# LCD.net
KiCad netlist of a schematic drawn in Altium Designer
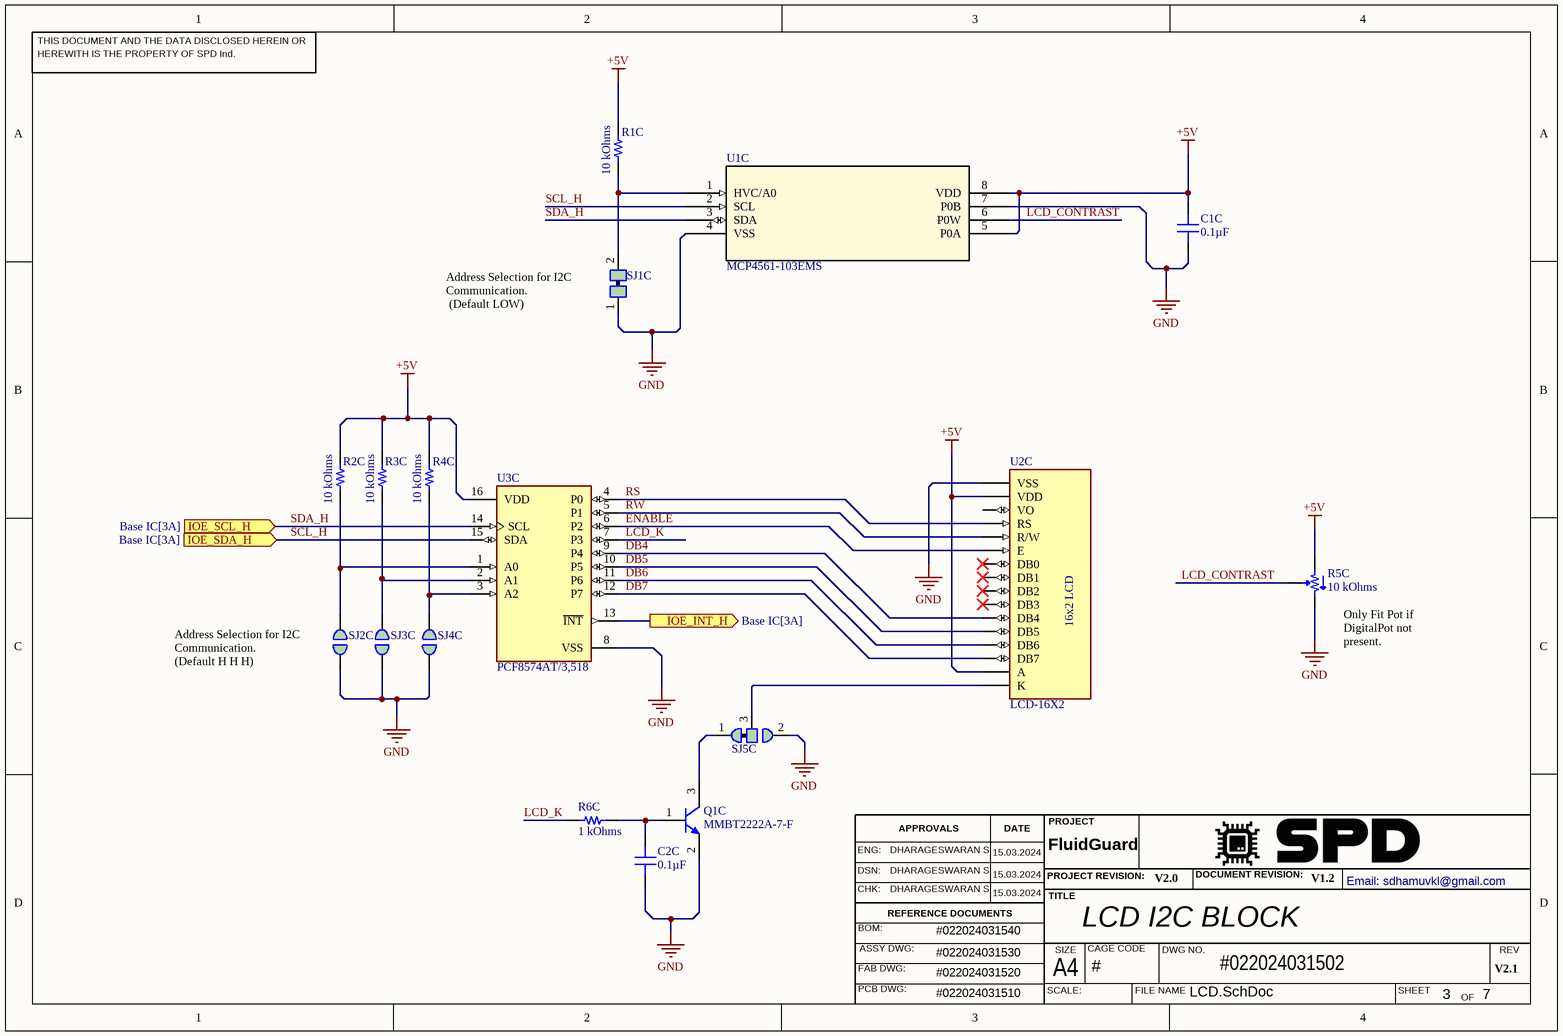
[diagram p0: LCD.SchDoc]

(export (version "E")
  (design (tool "Eeschema 10.0.6"))
  (components
    (comp (ref "C1C")
      (value "0.1µF")
      (footprint "CAP 0402_1005")
      (description "CAP CER 0.1UF 16V X7R 0402")
      (fields (field (name "PART NUMBER") "0402YC104KAT2A") (field (name "MANUFACTURER") "AVX Corporation"))
      (libsource (lib "Postgres Altium Library - altium_library") (part "Capacitor"))
    )
    (comp (ref "C2C")
      (value "0.1µF")
      (footprint "CAP 0402_1005")
      (description "CAP CER 0.1UF 16V X7R 0402")
      (fields (field (name "PART NUMBER") "0402YC104KAT2A") (field (name "MANUFACTURER") "AVX Corporation"))
      (libsource (lib "Postgres Altium Library - altium_library") (part "Capacitor"))
    )
    (comp (ref "Q1C")
      (value "MMBT2222A-7-F")
      (footprint "DIODES SOT-23-3")
      (description "TRANS NPN 40V 0.6A SOT23-3")
      (fields (field (name "MANUFACTURER") "Diodes Incorporated"))
      (libsource (lib "Postgres Altium Library - altium_library") (part "DIODES INC NPN SOT-23-3"))
    )
    (comp (ref "R1C")
      (value "10 kOhms")
      (footprint "RES 0402_1005")
      (description "RES 10K OHM 1% 1/16W 0402")
      (fields (field (name "PART NUMBER") "AC0402FR-1310KL") (field (name "TOLERANCE") "±1%"))
      (libsource (lib "Postgres Altium Library - altium_library") (part "Resistor"))
    )
    (comp (ref "R2C")
      (value "10 kOhms")
      (footprint "RES 0402_1005")
      (description "RES 10K OHM 1% 1/16W 0402")
      (fields (field (name "PART NUMBER") "AC0402FR-1310KL") (field (name "TOLERANCE") "±1%"))
      (libsource (lib "Postgres Altium Library - altium_library") (part "Resistor"))
    )
    (comp (ref "R3C")
      (value "10 kOhms")
      (footprint "RES 0402_1005")
      (description "RES 10K OHM 1% 1/16W 0402")
      (fields (field (name "PART NUMBER") "AC0402FR-1310KL") (field (name "TOLERANCE") "±1%"))
      (libsource (lib "Postgres Altium Library - altium_library") (part "Resistor"))
    )
    (comp (ref "R4C")
      (value "10 kOhms")
      (footprint "RES 0402_1005")
      (description "RES 10K OHM 1% 1/16W 0402")
      (fields (field (name "PART NUMBER") "AC0402FR-1310KL") (field (name "TOLERANCE") "±1%"))
      (libsource (lib "Postgres Altium Library - altium_library") (part "Resistor"))
    )
    (comp (ref "R5C")
      (value "10 kOhms")
      (footprint "BOURNS TRIMPOT 3299P")
      (description "TRIMMER 10K OHM 0.5W PC PIN SIDE")
      (fields (field (name "PART NUMBER") "3299P-1-103LF") (field (name "TOLERANCE") "±10%"))
      (libsource (lib "Postgres Altium Library - altium_library") (part "Potentiometer"))
    )
    (comp (ref "R6C")
      (value "1 kOhms")
      (footprint "RES 0402_1005")
      (description "RES 1K OHM 0.5% 1/16W 0402")
      (fields (field (name "PART NUMBER") "AC0402DR-071KL") (field (name "TOLERANCE") "±0.5%"))
      (libsource (lib "Postgres Altium Library - altium_library") (part "Resistor"))
    )
    (comp (ref "SJ1C")
      (value "2PIN")
      (footprint "Rectangular Jumper Joint")
      (libsource (lib "Jumper-SMD") (part "Regtangular Jumper Joint"))
    )
    (comp (ref "SJ2C")
      (value "2PIN")
      (footprint "Rounded Jumper")
      (libsource (lib "Jumper-SMD") (part "Rounded Jumper"))
    )
    (comp (ref "SJ3C")
      (value "2PIN")
      (footprint "Rounded Jumper")
      (libsource (lib "Jumper-SMD") (part "Rounded Jumper"))
    )
    (comp (ref "SJ4C")
      (value "2PIN")
      (footprint "Rounded Jumper")
      (libsource (lib "Jumper-SMD") (part "Rounded Jumper"))
    )
    (comp (ref "SJ5C")
      (value "3PIN")
      (footprint "Rounded Jumper Joint 3-pin")
      (libsource (lib "Jumper-SMD") (part "Rounded Jumper Joint 3-pin"))
    )
    (comp (ref "U1C")
      (value "MCP4561-103EMS")
      (footprint "MSOP8_MC_MCH")
      (description "No Description Available")
      (libsource (lib "MCP4561-103EMS") (part "MCP4561-103EMS"))
    )
    (comp (ref "U2C")
      (value "LCD-16X2")
      (footprint "LCD-16X2 Pin")
      (description "Display Development Tools 16x2 Black on Green Char LCD w Backlight")
      (fields (field (name "MF") "Gravitech"))
      (libsource (lib "LCD16X2_PIN") (part "LCD-16X2"))
    )
    (comp (ref "U3C")
      (value "PCF8574AT/3,518")
      (footprint "FP-SOT162-1-MFG")
      (description "IC I/O EXPANDER I2C 8B 16SOIC")
      (fields
        (field (name "MANUFACTURER") "NXP Semiconductors")
        (field (name "OCTOPART") "https://octopart.com/pcf8574at%2F3%2C518-nxp+semiconductors-11541925")
      )
      (libsource (lib "Altium Content Vault") (part "f7fde53ce59de981fb0b266a4e103eb"))
    )
  )
  (nets
    (net (code "1") (name "+5V") (class "Default")
      (node (ref "C1C") (pin "2") (pinfunction "2_2") (pintype "passive"))
      (node (ref "R1C") (pin "2") (pinfunction "2_2") (pintype "passive"))
      (node (ref "R2C") (pin "2") (pinfunction "2_2") (pintype "passive"))
      (node (ref "R3C") (pin "2") (pinfunction "2_2") (pintype "passive"))
      (node (ref "R4C") (pin "2") (pinfunction "2_2") (pintype "passive"))
      (node (ref "R5C") (pin "1") (pinfunction "1_1") (pintype "passive"))
      (node (ref "U1C") (pin "5") (pinfunction "P0A_5") (pintype "passive"))
      (node (ref "U1C") (pin "8") (pinfunction "VDD_8") (pintype "power_in"))
      (node (ref "U2C") (pin "15") (pinfunction "A_15") (pintype "power_in"))
      (node (ref "U2C") (pin "2") (pinfunction "VDD_2") (pintype "power_in"))
      (node (ref "U3C") (pin "16") (pinfunction "VDD_16") (pintype "power_in"))
    )
    (net (code "2") (name "/DB4") (class "Default")
      (node (ref "U2C") (pin "11") (pinfunction "DB4_11") (pintype "bidirectional"))
      (node (ref "U3C") (pin "9") (pinfunction "P4_9") (pintype "bidirectional"))
    )
    (net (code "3") (name "/DB5") (class "Default")
      (node (ref "U2C") (pin "12") (pinfunction "DB5_12") (pintype "bidirectional"))
      (node (ref "U3C") (pin "10") (pinfunction "P5_10") (pintype "bidirectional"))
    )
    (net (code "4") (name "/DB6") (class "Default")
      (node (ref "U2C") (pin "13") (pinfunction "DB6_13") (pintype "bidirectional"))
      (node (ref "U3C") (pin "11") (pinfunction "P6_11") (pintype "bidirectional"))
    )
    (net (code "5") (name "/DB7") (class "Default")
      (node (ref "U2C") (pin "14") (pinfunction "DB7_14") (pintype "bidirectional"))
      (node (ref "U3C") (pin "12") (pinfunction "P7_12") (pintype "bidirectional"))
    )
    (net (code "6") (name "/ENABLE") (class "Default")
      (node (ref "U2C") (pin "6") (pinfunction "E_6") (pintype "input"))
      (node (ref "U3C") (pin "6") (pinfunction "P2_6") (pintype "bidirectional"))
    )
    (net (code "7") (name "/IOE_INT_H") (class "Default")
      (node (ref "U3C") (pin "13") (pinfunction "~{INT}_13") (pintype "output"))
    )
    (net (code "8") (name "/LCD_CONTRAST") (class "Default")
      (node (ref "R5C") (pin "2") (pinfunction "2_2") (pintype "passive"))
      (node (ref "U1C") (pin "6") (pinfunction "P0W_6") (pintype "passive"))
    )
    (net (code "9") (name "/LCD_K") (class "Default")
      (node (ref "R6C") (pin "1") (pinfunction "1_1") (pintype "passive"))
      (node (ref "U3C") (pin "7") (pinfunction "P3_7") (pintype "bidirectional"))
    )
    (net (code "10") (name "/RS") (class "Default")
      (node (ref "U2C") (pin "4") (pinfunction "RS_4") (pintype "input"))
      (node (ref "U3C") (pin "4") (pinfunction "P0_4") (pintype "bidirectional"))
    )
    (net (code "11") (name "/RW") (class "Default")
      (node (ref "U2C") (pin "5") (pinfunction "R/W_5") (pintype "input"))
      (node (ref "U3C") (pin "5") (pinfunction "P1_5") (pintype "bidirectional"))
    )
    (net (code "12") (name "/SCL_H") (class "Default")
      (node (ref "U1C") (pin "2") (pinfunction "SCL_2") (pintype "input"))
      (node (ref "U3C") (pin "15") (pinfunction "SDA_15") (pintype "bidirectional"))
    )
    (net (code "13") (name "/SDA_H") (class "Default")
      (node (ref "U1C") (pin "3") (pinfunction "SDA_3") (pintype "bidirectional"))
      (node (ref "U3C") (pin "14") (pinfunction "SCL_14") (pintype "input"))
    )
    (net (code "14") (name "GND") (class "Default")
      (node (ref "C1C") (pin "1") (pinfunction "1_1") (pintype "passive"))
      (node (ref "C2C") (pin "1") (pinfunction "1_1") (pintype "passive"))
      (node (ref "Q1C") (pin "2") (pinfunction "E_2") (pintype "passive"))
      (node (ref "R5C") (pin "3") (pinfunction "3_3") (pintype "passive"))
      (node (ref "SJ1C") (pin "1") (pinfunction "1_1") (pintype "passive"))
      (node (ref "SJ2C") (pin "1") (pinfunction "1_1") (pintype "passive"))
      (node (ref "SJ3C") (pin "1") (pinfunction "1_1") (pintype "passive"))
      (node (ref "SJ4C") (pin "1") (pinfunction "1_1") (pintype "passive"))
      (node (ref "SJ5C") (pin "2") (pinfunction "2_2") (pintype "passive"))
      (node (ref "U1C") (pin "4") (pinfunction "VSS_4") (pintype "power_in"))
      (node (ref "U1C") (pin "7") (pinfunction "P0B_7") (pintype "passive"))
      (node (ref "U2C") (pin "1") (pinfunction "VSS_1") (pintype "power_in"))
      (node (ref "U3C") (pin "8") (pinfunction "VSS_8") (pintype "power_in"))
    )
    (net (code "15") (name "Net-(Q1C-B)") (class "Default")
      (node (ref "C2C") (pin "2") (pinfunction "2_2") (pintype "passive"))
      (node (ref "Q1C") (pin "1") (pinfunction "B_1") (pintype "passive"))
      (node (ref "R6C") (pin "2") (pinfunction "2_2") (pintype "passive"))
    )
    (net (code "16") (name "Net-(Q1C-C)") (class "Default")
      (node (ref "Q1C") (pin "3") (pinfunction "C_3") (pintype "passive"))
      (node (ref "SJ5C") (pin "1") (pinfunction "1_1") (pintype "passive"))
    )
    (net (code "17") (name "Net-(U1C-HVC{slash}A0)") (class "Default")
      (node (ref "R1C") (pin "1") (pinfunction "1_1") (pintype "passive"))
      (node (ref "SJ1C") (pin "2") (pinfunction "2_2") (pintype "passive"))
      (node (ref "U1C") (pin "1") (pinfunction "HVC/A0_1") (pintype "input"))
    )
    (net (code "18") (name "Net-(U2C-K)") (class "Default")
      (node (ref "SJ5C") (pin "3") (pinfunction "3_3") (pintype "passive"))
      (node (ref "U2C") (pin "16") (pinfunction "K_16") (pintype "power_in"))
    )
    (net (code "19") (name "Net-(U3C-A0)") (class "Default")
      (node (ref "R2C") (pin "1") (pinfunction "1_1") (pintype "passive"))
      (node (ref "SJ2C") (pin "2") (pinfunction "2_2") (pintype "passive"))
      (node (ref "U3C") (pin "1") (pinfunction "A0_1") (pintype "input"))
    )
    (net (code "20") (name "Net-(U3C-A1)") (class "Default")
      (node (ref "R3C") (pin "1") (pinfunction "1_1") (pintype "passive"))
      (node (ref "SJ3C") (pin "2") (pinfunction "2_2") (pintype "passive"))
      (node (ref "U3C") (pin "2") (pinfunction "A1_2") (pintype "input"))
    )
    (net (code "21") (name "Net-(U3C-A2)") (class "Default")
      (node (ref "R4C") (pin "1") (pinfunction "1_1") (pintype "passive"))
      (node (ref "SJ4C") (pin "2") (pinfunction "2_2") (pintype "passive"))
      (node (ref "U3C") (pin "3") (pinfunction "A2_3") (pintype "input"))
    )
    (net (code "22") (name "unconnected-(U2C-DB0-Pad7)") (class "Default")
      (node (ref "U2C") (pin "7") (pinfunction "DB0_7") (pintype "bidirectional+no_connect"))
    )
    (net (code "23") (name "unconnected-(U2C-DB1-Pad8)") (class "Default")
      (node (ref "U2C") (pin "8") (pinfunction "DB1_8") (pintype "bidirectional+no_connect"))
    )
    (net (code "24") (name "unconnected-(U2C-DB2-Pad9)") (class "Default")
      (node (ref "U2C") (pin "9") (pinfunction "DB2_9") (pintype "bidirectional+no_connect"))
    )
    (net (code "25") (name "unconnected-(U2C-DB3-Pad10)") (class "Default")
      (node (ref "U2C") (pin "10") (pinfunction "DB3_10") (pintype "bidirectional+no_connect"))
    )
    (net (code "26") (name "unconnected-(U2C-VO-Pad3)") (class "Default")
      (node (ref "U2C") (pin "3") (pinfunction "VO_3") (pintype "bidirectional"))
    )
  )
)
